# as3320-Bandpass.net
KiCad netlist of a schematic drawn in EAGLE
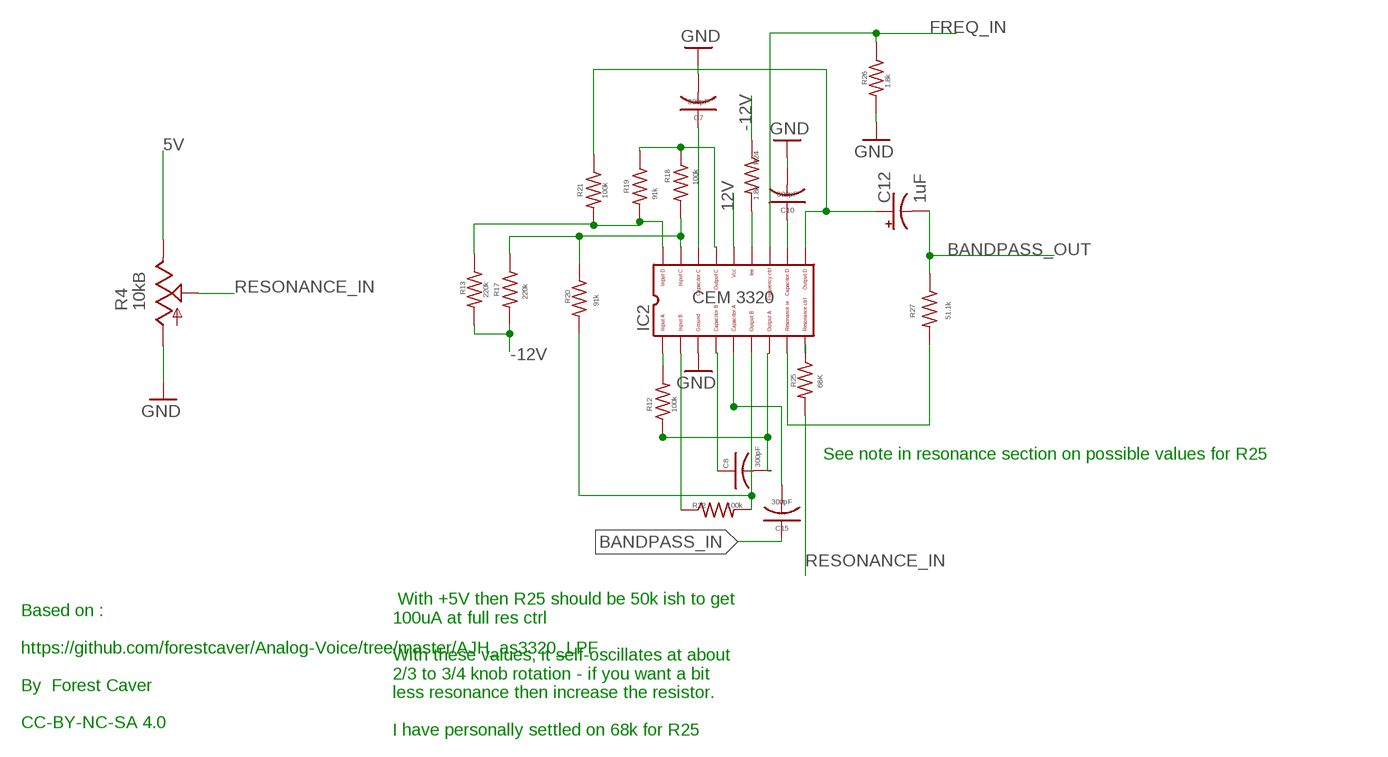
[diagram p0: schematic, sheet 1]
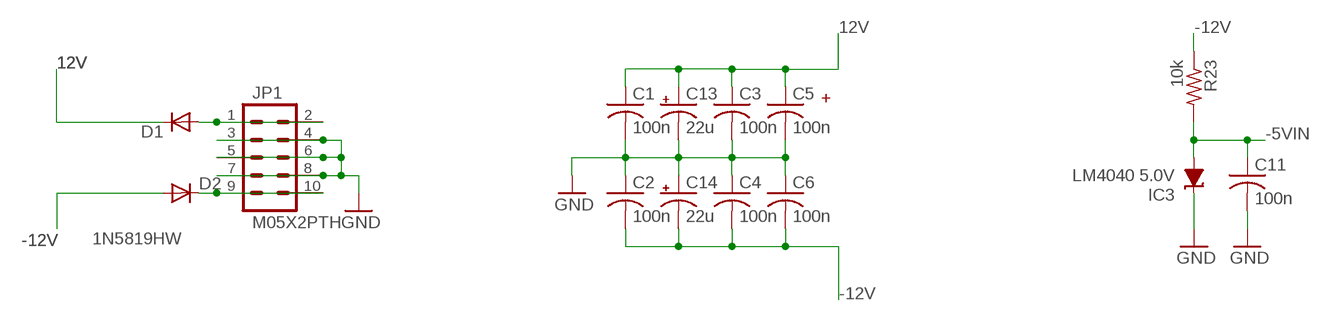
[diagram p1: schematic, sheet 2]
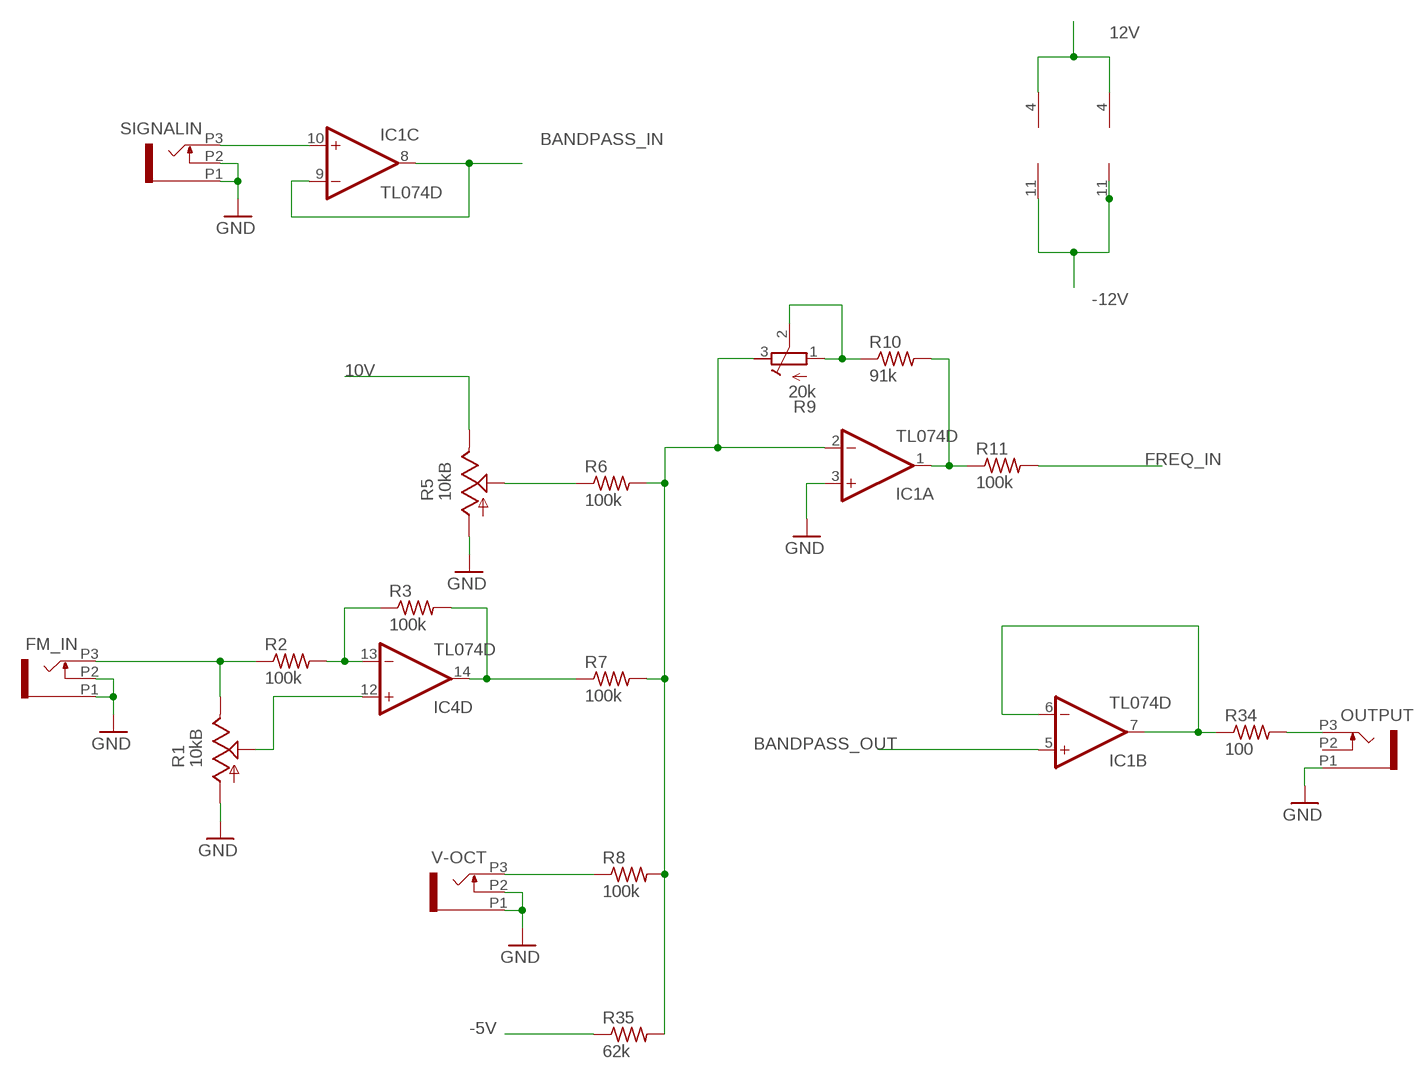
[diagram p2: schematic, sheet 3]
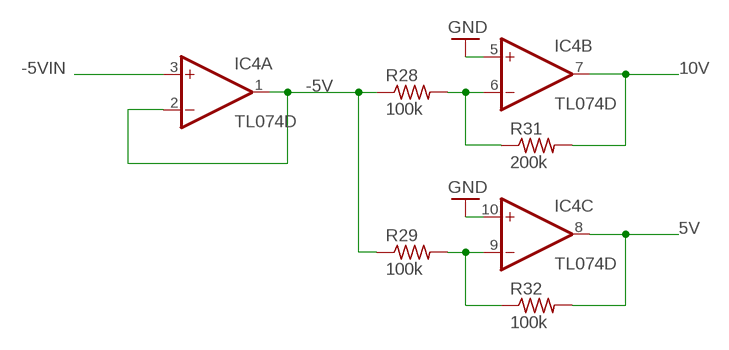
[diagram p3: schematic, sheet 4]

(export (version "E")
  (design (tool "Eeschema 10.0.6"))
  (components
    (comp (ref "IC4")
      (value "TL074D")
      (footprint "eagle-import:SO14")
      (libsource (lib "eagle-import") (part "TL074D"))
    )
    (comp (ref "R28")
      (value "100k")
      (footprint "eagle-import:R0603")
      (libsource (lib "eagle-import") (part "resistor_R-US_R0603"))
    )
    (comp (ref "R29")
      (value "100k")
      (footprint "eagle-import:R0603")
      (libsource (lib "eagle-import") (part "resistor_R-US_R0603"))
    )
    (comp (ref "R31")
      (value "200k")
      (footprint "eagle-import:R0603")
      (libsource (lib "eagle-import") (part "resistor_R-US_R0603"))
    )
    (comp (ref "R32")
      (value "100k")
      (footprint "eagle-import:R0603")
      (libsource (lib "eagle-import") (part "resistor_R-US_R0603"))
    )
    (comp (ref "FM_IN")
      (value "PJ301_THONKICONN6")
      (footprint "eagle-import:WQP_PJ_301M6")
      (libsource (lib "eagle-import") (part "PJ301_THONKICONN6"))
    )
    (comp (ref "IC1")
      (value "TL074D")
      (footprint "eagle-import:SO14")
      (libsource (lib "eagle-import") (part "TL074D"))
    )
    (comp (ref "OUTPUT")
      (value "PJ301_THONKICONN6")
      (footprint "eagle-import:WQP_PJ_301M6")
      (libsource (lib "eagle-import") (part "PJ301_THONKICONN6"))
    )
    (comp (ref "R1")
      (value "10kB")
      (footprint "eagle-import:ALPS_POT_VERTICAL")
      (libsource (lib "eagle-import") (part "POT_USVERTICAL"))
    )
    (comp (ref "R2")
      (value "100k")
      (footprint "eagle-import:R0603")
      (libsource (lib "eagle-import") (part "resistor_R-US_R0603"))
    )
    (comp (ref "R3")
      (value "100k")
      (footprint "eagle-import:R0603")
      (libsource (lib "eagle-import") (part "resistor_R-US_R0603"))
    )
    (comp (ref "R5")
      (value "10kB")
      (footprint "eagle-import:ALPS_POT_VERTICAL")
      (libsource (lib "eagle-import") (part "POT_USVERTICAL"))
    )
    (comp (ref "R6")
      (value "100k")
      (footprint "eagle-import:R0603")
      (libsource (lib "eagle-import") (part "resistor_R-US_R0603"))
    )
    (comp (ref "R7")
      (value "100k")
      (footprint "eagle-import:R0603")
      (libsource (lib "eagle-import") (part "resistor_R-US_R0603"))
    )
    (comp (ref "R8")
      (value "100k")
      (footprint "eagle-import:R0603")
      (libsource (lib "eagle-import") (part "resistor_R-US_R0603"))
    )
    (comp (ref "R9")
      (value "20k")
      (footprint "eagle-import:RTRIM3296X")
      (libsource (lib "eagle-import") (part "R-TRIMM3296X"))
    )
    (comp (ref "R10")
      (value "91k")
      (footprint "eagle-import:R0603")
      (libsource (lib "eagle-import") (part "resistor_R-US_R0603"))
    )
    (comp (ref "R11")
      (value "100k")
      (footprint "eagle-import:R0603")
      (libsource (lib "eagle-import") (part "resistor_R-US_R0603"))
    )
    (comp (ref "R34")
      (value "100")
      (footprint "eagle-import:R0603")
      (libsource (lib "eagle-import") (part "resistor_R-US_R0603"))
    )
    (comp (ref "R35")
      (value "62k")
      (footprint "eagle-import:R0603")
      (libsource (lib "eagle-import") (part "resistor_R-US_R0603"))
    )
    (comp (ref "SIGNALIN")
      (value "PJ301_THONKICONN6")
      (footprint "eagle-import:WQP_PJ_301M6")
      (libsource (lib "eagle-import") (part "PJ301_THONKICONN6"))
    )
    (comp (ref "V-OCT")
      (value "PJ301_THONKICONN6")
      (footprint "eagle-import:WQP_PJ_301M6")
      (libsource (lib "eagle-import") (part "PJ301_THONKICONN6"))
    )
    (comp (ref "C1")
      (value "100n")
      (footprint "eagle-import:C0603")
      (libsource (lib "eagle-import") (part "C-USC0603"))
    )
    (comp (ref "C2")
      (value "100n")
      (footprint "eagle-import:C0603")
      (libsource (lib "eagle-import") (part "C-USC0603"))
    )
    (comp (ref "C3")
      (value "100n")
      (footprint "eagle-import:C0603")
      (libsource (lib "eagle-import") (part "C-USC0603"))
    )
    (comp (ref "C4")
      (value "100n")
      (footprint "eagle-import:C0603")
      (libsource (lib "eagle-import") (part "C-USC0603"))
    )
    (comp (ref "C5")
      (value "100n")
      (footprint "eagle-import:C0603")
      (libsource (lib "eagle-import") (part "C-USC0603"))
    )
    (comp (ref "C6")
      (value "100n")
      (footprint "eagle-import:C0603")
      (libsource (lib "eagle-import") (part "C-USC0603"))
    )
    (comp (ref "C11")
      (value "100n")
      (footprint "eagle-import:C0603")
      (libsource (lib "eagle-import") (part "C-USC0603"))
    )
    (comp (ref "C13")
      (value "22u")
      (footprint "eagle-import:PANASONIC_B")
      (libsource (lib "eagle-import") (part "CPOL-USB"))
    )
    (comp (ref "C14")
      (value "22u")
      (footprint "eagle-import:PANASONIC_B")
      (libsource (lib "eagle-import") (part "CPOL-USB"))
    )
    (comp (ref "D1")
      (value "1N5819HW")
      (footprint "eagle-import:SOD123")
      (libsource (lib "eagle-import") (part "DIODE-SOD123"))
    )
    (comp (ref "D2")
      (value "1N5819HW")
      (footprint "eagle-import:SOD123")
      (libsource (lib "eagle-import") (part "DIODE-SOD123"))
    )
    (comp (ref "IC3")
      (value "LM4040 5.0V")
      (footprint "eagle-import:DBZ_R-PDSO-G3")
      (libsource (lib "eagle-import") (part "LM4041DBZC12"))
    )
    (comp (ref "JP1")
      (value "M05X2PTH")
      (footprint "eagle-import:AVR_ICSP")
      (libsource (lib "eagle-import") (part "M05X2PTH"))
    )
    (comp (ref "R23")
      (value "10k")
      (footprint "eagle-import:R0603")
      (libsource (lib "eagle-import") (part "resistor_R-US_R0603"))
    )
    (comp (ref "C7")
      (value "300pF")
      (footprint "eagle-import:C0603")
      (libsource (lib "eagle-import") (part "rcl_334_C-USC0603"))
    )
    (comp (ref "C8")
      (value "300pF")
      (footprint "eagle-import:C0603")
      (libsource (lib "eagle-import") (part "rcl_334_C-USC0603"))
    )
    (comp (ref "C10")
      (value "300pF")
      (footprint "eagle-import:C0603")
      (libsource (lib "eagle-import") (part "rcl_334_C-USC0603"))
    )
    (comp (ref "C12")
      (value "1uF")
      (footprint "eagle-import:PANASONIC_B")
      (libsource (lib "eagle-import") (part "rcl_334_CPOL-USB"))
    )
    (comp (ref "C15")
      (value "300pF")
      (footprint "eagle-import:C0603")
      (libsource (lib "eagle-import") (part "rcl_334_C-USC0603"))
    )
    (comp (ref "IC2")
      (value "CEM3320")
      (footprint "eagle-import:DIL18")
      (libsource (lib "eagle-import") (part "CEM3320"))
    )
    (comp (ref "R4")
      (value "10kB")
      (footprint "eagle-import:ALPS_POT_VERTICAL")
      (libsource (lib "eagle-import") (part "POT_USVERTICAL"))
    )
    (comp (ref "R12")
      (value "100k")
      (footprint "eagle-import:R0603")
      (libsource (lib "eagle-import") (part "R-US_R0603"))
    )
    (comp (ref "R13")
      (value "220k")
      (footprint "eagle-import:R0603")
      (libsource (lib "eagle-import") (part "R-US_R0603"))
    )
    (comp (ref "R17")
      (value "220k")
      (footprint "eagle-import:R0603")
      (libsource (lib "eagle-import") (part "R-US_R0603"))
    )
    (comp (ref "R18")
      (value "100k")
      (footprint "eagle-import:R0603")
      (libsource (lib "eagle-import") (part "R-US_R0603"))
    )
    (comp (ref "R19")
      (value "91k")
      (footprint "eagle-import:R0603")
      (libsource (lib "eagle-import") (part "R-US_R0603"))
    )
    (comp (ref "R20")
      (value "91k")
      (footprint "eagle-import:R0603")
      (libsource (lib "eagle-import") (part "R-US_R0603"))
    )
    (comp (ref "R21")
      (value "100k")
      (footprint "eagle-import:R0603")
      (libsource (lib "eagle-import") (part "R-US_R0603"))
    )
    (comp (ref "R22")
      (value "100k")
      (footprint "eagle-import:R0603")
      (libsource (lib "eagle-import") (part "R-US_R0603"))
    )
    (comp (ref "R24")
      (value "1.8k")
      (footprint "eagle-import:R0603")
      (libsource (lib "eagle-import") (part "R-US_R0603"))
    )
    (comp (ref "R25")
      (value "68K")
      (footprint "eagle-import:R0603")
      (libsource (lib "eagle-import") (part "R-US_R0603"))
    )
    (comp (ref "R26")
      (value "1.8k")
      (footprint "eagle-import:R0603")
      (libsource (lib "eagle-import") (part "R-US_R0603"))
    )
    (comp (ref "R27")
      (value "51.1k")
      (footprint "eagle-import:R0603")
      (libsource (lib "eagle-import") (part "R-US_R0603"))
    )
  )
  (nets
    (net (code "1") (name "-5V") (class "Default")
      (node (ref "IC4") (pin "1") (pinfunction "OUT_1") (pintype "output"))
      (node (ref "IC4") (pin "2") (pinfunction "-IN_2") (pintype "input"))
      (node (ref "R28") (pin "1") (pinfunction "1_1") (pintype "passive"))
      (node (ref "R29") (pin "1") (pinfunction "1_1") (pintype "passive"))
      (node (ref "R35") (pin "1") (pinfunction "1_1") (pintype "passive"))
    )
    (net (code "2") (name "-5VIN") (class "Default")
      (node (ref "C11") (pin "1") (pinfunction "1_1") (pintype "passive"))
      (node (ref "IC3") (pin "2") (pinfunction "A_2") (pintype "passive"))
      (node (ref "IC4") (pin "3") (pinfunction "+IN_3") (pintype "input"))
      (node (ref "R23") (pin "2") (pinfunction "2_2") (pintype "passive"))
    )
    (net (code "3") (name "-12V") (class "Default")
      (node (ref "C14") (pin "-") (pinfunction "-_-") (pintype "passive"))
      (node (ref "C2") (pin "2") (pinfunction "2_2") (pintype "passive"))
      (node (ref "C4") (pin "2") (pinfunction "2_2") (pintype "passive"))
      (node (ref "C6") (pin "2") (pinfunction "2_2") (pintype "passive"))
      (node (ref "D2") (pin "A") (pinfunction "A_A") (pintype "passive"))
      (node (ref "IC1") (pin "11") (pinfunction "V-_11") (pintype "power_in"))
      (node (ref "IC4") (pin "11") (pinfunction "V-_11") (pintype "power_in"))
      (node (ref "R13") (pin "2") (pinfunction "2_2") (pintype "passive"))
      (node (ref "R17") (pin "2") (pinfunction "2_2") (pintype "passive"))
      (node (ref "R23") (pin "1") (pinfunction "1_1") (pintype "passive"))
      (node (ref "R24") (pin "1") (pinfunction "1_1") (pintype "passive"))
    )
    (net (code "4") (name "5V") (class "Default")
      (node (ref "IC4") (pin "8") (pinfunction "OUT_8") (pintype "output"))
      (node (ref "R32") (pin "2") (pinfunction "2_2") (pintype "passive"))
      (node (ref "R4") (pin "P$1") (pinfunction "E_P$1") (pintype "passive"))
    )
    (net (code "5") (name "10V") (class "Default")
      (node (ref "IC4") (pin "7") (pinfunction "OUT_7") (pintype "output"))
      (node (ref "R31") (pin "2") (pinfunction "2_2") (pintype "passive"))
      (node (ref "R5") (pin "P$1") (pinfunction "E_P$1") (pintype "passive"))
    )
    (net (code "6") (name "12V") (class "Default")
      (node (ref "C1") (pin "1") (pinfunction "1_1") (pintype "passive"))
      (node (ref "C13") (pin "+") (pinfunction "+_+") (pintype "passive"))
      (node (ref "C3") (pin "1") (pinfunction "1_1") (pintype "passive"))
      (node (ref "C5") (pin "1") (pinfunction "1_1") (pintype "passive"))
      (node (ref "D1") (pin "C") (pinfunction "C_C") (pintype "passive"))
      (node (ref "IC1") (pin "4") (pinfunction "V+_4") (pintype "power_in"))
      (node (ref "IC2") (pin "14") (pinfunction "14_14") (pintype "power_in"))
      (node (ref "IC4") (pin "4") (pinfunction "V+_4") (pintype "power_in"))
    )
    (net (code "7") (name "BANDPASS_IN") (class "Default")
      (node (ref "C15") (pin "1") (pinfunction "1_1") (pintype "passive"))
      (node (ref "IC1") (pin "8") (pinfunction "OUT_8") (pintype "output"))
      (node (ref "IC1") (pin "9") (pinfunction "-IN_9") (pintype "input"))
    )
    (net (code "8") (name "BANDPASS_OUT") (class "Default")
      (node (ref "C12") (pin "-") (pinfunction "-_-") (pintype "passive"))
      (node (ref "IC1") (pin "5") (pinfunction "+IN_5") (pintype "input"))
      (node (ref "R27") (pin "1") (pinfunction "1_1") (pintype "passive"))
    )
    (net (code "9") (name "FREQ_IN") (class "Default")
      (node (ref "IC2") (pin "12") (pinfunction "12_12") (pintype "bidirectional"))
      (node (ref "R11") (pin "2") (pinfunction "2_2") (pintype "passive"))
      (node (ref "R26") (pin "1") (pinfunction "1_1") (pintype "passive"))
    )
    (net (code "10") (name "GND") (class "Default")
      (node (ref "C1") (pin "2") (pinfunction "2_2") (pintype "passive"))
      (node (ref "C10") (pin "2") (pinfunction "2_2") (pintype "passive"))
      (node (ref "C11") (pin "2") (pinfunction "2_2") (pintype "passive"))
      (node (ref "C13") (pin "-") (pinfunction "-_-") (pintype "passive"))
      (node (ref "C14") (pin "+") (pinfunction "+_+") (pintype "passive"))
      (node (ref "C2") (pin "1") (pinfunction "1_1") (pintype "passive"))
      (node (ref "C3") (pin "2") (pinfunction "2_2") (pintype "passive"))
      (node (ref "C4") (pin "1") (pinfunction "1_1") (pintype "passive"))
      (node (ref "C5") (pin "2") (pinfunction "2_2") (pintype "passive"))
      (node (ref "C6") (pin "1") (pinfunction "1_1") (pintype "passive"))
      (node (ref "C7") (pin "2") (pinfunction "2_2") (pintype "passive"))
      (node (ref "FM_IN") (pin "P1") (pinfunction "1_P1") (pintype "passive"))
      (node (ref "FM_IN") (pin "P2") (pinfunction "2_P2") (pintype "passive"))
      (node (ref "IC1") (pin "3") (pinfunction "+IN_3") (pintype "input"))
      (node (ref "IC2") (pin "3") (pinfunction "3_3") (pintype "power_in"))
      (node (ref "IC3") (pin "1") (pinfunction "C_1") (pintype "passive"))
      (node (ref "IC4") (pin "10") (pinfunction "+IN_10") (pintype "input"))
      (node (ref "IC4") (pin "5") (pinfunction "+IN_5") (pintype "input"))
      (node (ref "JP1") (pin "3") (pinfunction "3_3") (pintype "passive"))
      (node (ref "JP1") (pin "4") (pinfunction "4_4") (pintype "passive"))
      (node (ref "JP1") (pin "5") (pinfunction "5_5") (pintype "passive"))
      (node (ref "JP1") (pin "6") (pinfunction "6_6") (pintype "passive"))
      (node (ref "JP1") (pin "7") (pinfunction "7_7") (pintype "passive"))
      (node (ref "JP1") (pin "8") (pinfunction "8_8") (pintype "passive"))
      (node (ref "OUTPUT") (pin "P1") (pinfunction "1_P1") (pintype "passive"))
      (node (ref "R1") (pin "P$3") (pinfunction "A_P$3") (pintype "passive"))
      (node (ref "R26") (pin "2") (pinfunction "2_2") (pintype "passive"))
      (node (ref "R4") (pin "P$3") (pinfunction "A_P$3") (pintype "passive"))
      (node (ref "R5") (pin "P$3") (pinfunction "A_P$3") (pintype "passive"))
      (node (ref "SIGNALIN") (pin "P1") (pinfunction "1_P1") (pintype "passive"))
      (node (ref "SIGNALIN") (pin "P2") (pinfunction "2_P2") (pintype "passive"))
      (node (ref "V-OCT") (pin "P1") (pinfunction "1_P1") (pintype "passive"))
      (node (ref "V-OCT") (pin "P2") (pinfunction "2_P2") (pintype "passive"))
    )
    (net (code "11") (name "Net-(C7-Pad1)") (class "Default")
      (node (ref "C7") (pin "1") (pinfunction "1_1") (pintype "passive"))
      (node (ref "IC2") (pin "16") (pinfunction "16_16") (pintype "bidirectional"))
    )
    (net (code "12") (name "Net-(C8-Pad1)") (class "Default")
      (node (ref "C8") (pin "1") (pinfunction "1_1") (pintype "passive"))
      (node (ref "IC2") (pin "4") (pinfunction "4_4") (pintype "bidirectional"))
    )
    (net (code "13") (name "Net-(C8-Pad2)") (class "Default")
      (node (ref "C8") (pin "2") (pinfunction "2_2") (pintype "passive"))
      (node (ref "IC2") (pin "7") (pinfunction "7_7") (pintype "output"))
      (node (ref "R12") (pin "1") (pinfunction "1_1") (pintype "passive"))
    )
    (net (code "14") (name "Net-(C10-Pad1)") (class "Default")
      (node (ref "C10") (pin "1") (pinfunction "1_1") (pintype "passive"))
      (node (ref "IC2") (pin "11") (pinfunction "11_11") (pintype "output"))
    )
    (net (code "15") (name "Net-(C12-Pad+)") (class "Default")
      (node (ref "C12") (pin "+") (pinfunction "+_+") (pintype "passive"))
      (node (ref "IC2") (pin "10") (pinfunction "10_10") (pintype "output"))
      (node (ref "R21") (pin "1") (pinfunction "1_1") (pintype "passive"))
    )
    (net (code "16") (name "Net-(C15-Pad2)") (class "Default")
      (node (ref "C15") (pin "2") (pinfunction "2_2") (pintype "passive"))
      (node (ref "IC2") (pin "5") (pinfunction "5_5") (pintype "bidirectional"))
    )
    (net (code "17") (name "Net-(D1-PadA)") (class "Default")
      (node (ref "D1") (pin "A") (pinfunction "A_A") (pintype "passive"))
      (node (ref "JP1") (pin "1") (pinfunction "1_1") (pintype "passive"))
      (node (ref "JP1") (pin "2") (pinfunction "2_2") (pintype "passive"))
    )
    (net (code "18") (name "Net-(D2-PadC)") (class "Default")
      (node (ref "D2") (pin "C") (pinfunction "C_C") (pintype "passive"))
      (node (ref "JP1") (pin "10") (pinfunction "10_10") (pintype "passive"))
      (node (ref "JP1") (pin "9") (pinfunction "9_9") (pintype "passive"))
    )
    (net (code "19") (name "Net-(FM_IN-3)") (class "Default")
      (node (ref "FM_IN") (pin "P3") (pinfunction "3_P3") (pintype "passive"))
      (node (ref "R1") (pin "P$1") (pinfunction "E_P$1") (pintype "passive"))
      (node (ref "R2") (pin "1") (pinfunction "1_1") (pintype "passive"))
    )
    (net (code "20") (name "Net-(IC1A--IN)") (class "Default")
      (node (ref "IC1") (pin "2") (pinfunction "-IN_2") (pintype "input"))
      (node (ref "R35") (pin "2") (pinfunction "2_2") (pintype "passive"))
      (node (ref "R6") (pin "2") (pinfunction "2_2") (pintype "passive"))
      (node (ref "R7") (pin "2") (pinfunction "2_2") (pintype "passive"))
      (node (ref "R8") (pin "2") (pinfunction "2_2") (pintype "passive"))
      (node (ref "R9") (pin "3") (pinfunction "A_3") (pintype "passive"))
    )
    (net (code "21") (name "Net-(IC1A-OUT)") (class "Default")
      (node (ref "IC1") (pin "1") (pinfunction "OUT_1") (pintype "output"))
      (node (ref "R10") (pin "2") (pinfunction "2_2") (pintype "passive"))
      (node (ref "R11") (pin "1") (pinfunction "1_1") (pintype "passive"))
    )
    (net (code "22") (name "Net-(IC1B--IN)") (class "Default")
      (node (ref "IC1") (pin "6") (pinfunction "-IN_6") (pintype "input"))
      (node (ref "IC1") (pin "7") (pinfunction "OUT_7") (pintype "output"))
      (node (ref "R34") (pin "1") (pinfunction "1_1") (pintype "passive"))
    )
    (net (code "23") (name "Net-(IC1C-+IN)") (class "Default")
      (node (ref "IC1") (pin "10") (pinfunction "+IN_10") (pintype "input"))
      (node (ref "SIGNALIN") (pin "P3") (pinfunction "3_P3") (pintype "passive"))
    )
    (net (code "24") (name "Net-(IC2-Pad1)") (class "Default")
      (node (ref "IC2") (pin "1") (pinfunction "1_1") (pintype "input"))
      (node (ref "R12") (pin "2") (pinfunction "2_2") (pintype "passive"))
    )
    (net (code "25") (name "Net-(IC2-Pad2)") (class "Default")
      (node (ref "IC2") (pin "2") (pinfunction "2_2") (pintype "input"))
      (node (ref "R22") (pin "1") (pinfunction "1_1") (pintype "passive"))
    )
    (net (code "26") (name "Net-(IC2-Pad6)") (class "Default")
      (node (ref "IC2") (pin "6") (pinfunction "6_6") (pintype "output"))
      (node (ref "R20") (pin "2") (pinfunction "2_2") (pintype "passive"))
      (node (ref "R22") (pin "2") (pinfunction "2_2") (pintype "passive"))
    )
    (net (code "27") (name "Net-(IC2-Pad8)") (class "Default")
      (node (ref "IC2") (pin "8") (pinfunction "8_8") (pintype "input"))
      (node (ref "R27") (pin "2") (pinfunction "2_2") (pintype "passive"))
    )
    (net (code "28") (name "Net-(IC2-Pad9)") (class "Default")
      (node (ref "IC2") (pin "9") (pinfunction "9_9") (pintype "input"))
      (node (ref "R25") (pin "1") (pinfunction "1_1") (pintype "passive"))
    )
    (net (code "29") (name "Net-(IC2-Pad13)") (class "Default")
      (node (ref "IC2") (pin "13") (pinfunction "13_13") (pintype "power_in"))
      (node (ref "R24") (pin "2") (pinfunction "2_2") (pintype "passive"))
    )
    (net (code "30") (name "Net-(IC2-Pad15)") (class "Default")
      (node (ref "IC2") (pin "15") (pinfunction "15_15") (pintype "output"))
      (node (ref "R18") (pin "1") (pinfunction "1_1") (pintype "passive"))
      (node (ref "R19") (pin "1") (pinfunction "1_1") (pintype "passive"))
    )
    (net (code "31") (name "Net-(IC2-Pad17)") (class "Default")
      (node (ref "IC2") (pin "17") (pinfunction "17_17") (pintype "input"))
      (node (ref "R17") (pin "1") (pinfunction "1_1") (pintype "passive"))
      (node (ref "R18") (pin "2") (pinfunction "2_2") (pintype "passive"))
      (node (ref "R20") (pin "1") (pinfunction "1_1") (pintype "passive"))
    )
    (net (code "32") (name "Net-(IC2-Pad18)") (class "Default")
      (node (ref "IC2") (pin "18") (pinfunction "18_18") (pintype "input"))
      (node (ref "R13") (pin "1") (pinfunction "1_1") (pintype "passive"))
      (node (ref "R19") (pin "2") (pinfunction "2_2") (pintype "passive"))
      (node (ref "R21") (pin "2") (pinfunction "2_2") (pintype "passive"))
    )
    (net (code "33") (name "Net-(IC4B--IN)") (class "Default")
      (node (ref "IC4") (pin "6") (pinfunction "-IN_6") (pintype "input"))
      (node (ref "R28") (pin "2") (pinfunction "2_2") (pintype "passive"))
      (node (ref "R31") (pin "1") (pinfunction "1_1") (pintype "passive"))
    )
    (net (code "34") (name "Net-(IC4C--IN)") (class "Default")
      (node (ref "IC4") (pin "9") (pinfunction "-IN_9") (pintype "input"))
      (node (ref "R29") (pin "2") (pinfunction "2_2") (pintype "passive"))
      (node (ref "R32") (pin "1") (pinfunction "1_1") (pintype "passive"))
    )
    (net (code "35") (name "Net-(IC4D-+IN)") (class "Default")
      (node (ref "IC4") (pin "12") (pinfunction "+IN_12") (pintype "input"))
      (node (ref "R1") (pin "P$2") (pinfunction "S_P$2") (pintype "passive"))
    )
    (net (code "36") (name "Net-(IC4D--IN)") (class "Default")
      (node (ref "IC4") (pin "13") (pinfunction "-IN_13") (pintype "input"))
      (node (ref "R2") (pin "2") (pinfunction "2_2") (pintype "passive"))
      (node (ref "R3") (pin "1") (pinfunction "1_1") (pintype "passive"))
    )
    (net (code "37") (name "Net-(IC4D-OUT)") (class "Default")
      (node (ref "IC4") (pin "14") (pinfunction "OUT_14") (pintype "output"))
      (node (ref "R3") (pin "2") (pinfunction "2_2") (pintype "passive"))
      (node (ref "R7") (pin "1") (pinfunction "1_1") (pintype "passive"))
    )
    (net (code "38") (name "Net-(OUTPUT-3)") (class "Default")
      (node (ref "OUTPUT") (pin "P3") (pinfunction "3_P3") (pintype "passive"))
      (node (ref "R34") (pin "2") (pinfunction "2_2") (pintype "passive"))
    )
    (net (code "39") (name "Net-(R5-S)") (class "Default")
      (node (ref "R5") (pin "P$2") (pinfunction "S_P$2") (pintype "passive"))
      (node (ref "R6") (pin "1") (pinfunction "1_1") (pintype "passive"))
    )
    (net (code "40") (name "Net-(R9-E)") (class "Default")
      (node (ref "R10") (pin "1") (pinfunction "1_1") (pintype "passive"))
      (node (ref "R9") (pin "1") (pinfunction "E_1") (pintype "passive"))
      (node (ref "R9") (pin "2") (pinfunction "S_2") (pintype "passive"))
    )
    (net (code "41") (name "Net-(V-OCT-3)") (class "Default")
      (node (ref "R8") (pin "1") (pinfunction "1_1") (pintype "passive"))
      (node (ref "V-OCT") (pin "P3") (pinfunction "3_P3") (pintype "passive"))
    )
    (net (code "42") (name "RESONANCE_IN") (class "Default")
      (node (ref "R25") (pin "2") (pinfunction "2_2") (pintype "passive"))
      (node (ref "R4") (pin "P$2") (pinfunction "S_P$2") (pintype "passive"))
    )
    (net (code "43") (name "unconnected-(OUTPUT-2-PadP2)") (class "Default")
      (node (ref "OUTPUT") (pin "P2") (pinfunction "2_P2") (pintype "passive"))
    )
  )
)
